# SCH_HOME_2023-08-20.net
KiCad netlist of a schematic drawn in EasyEDA
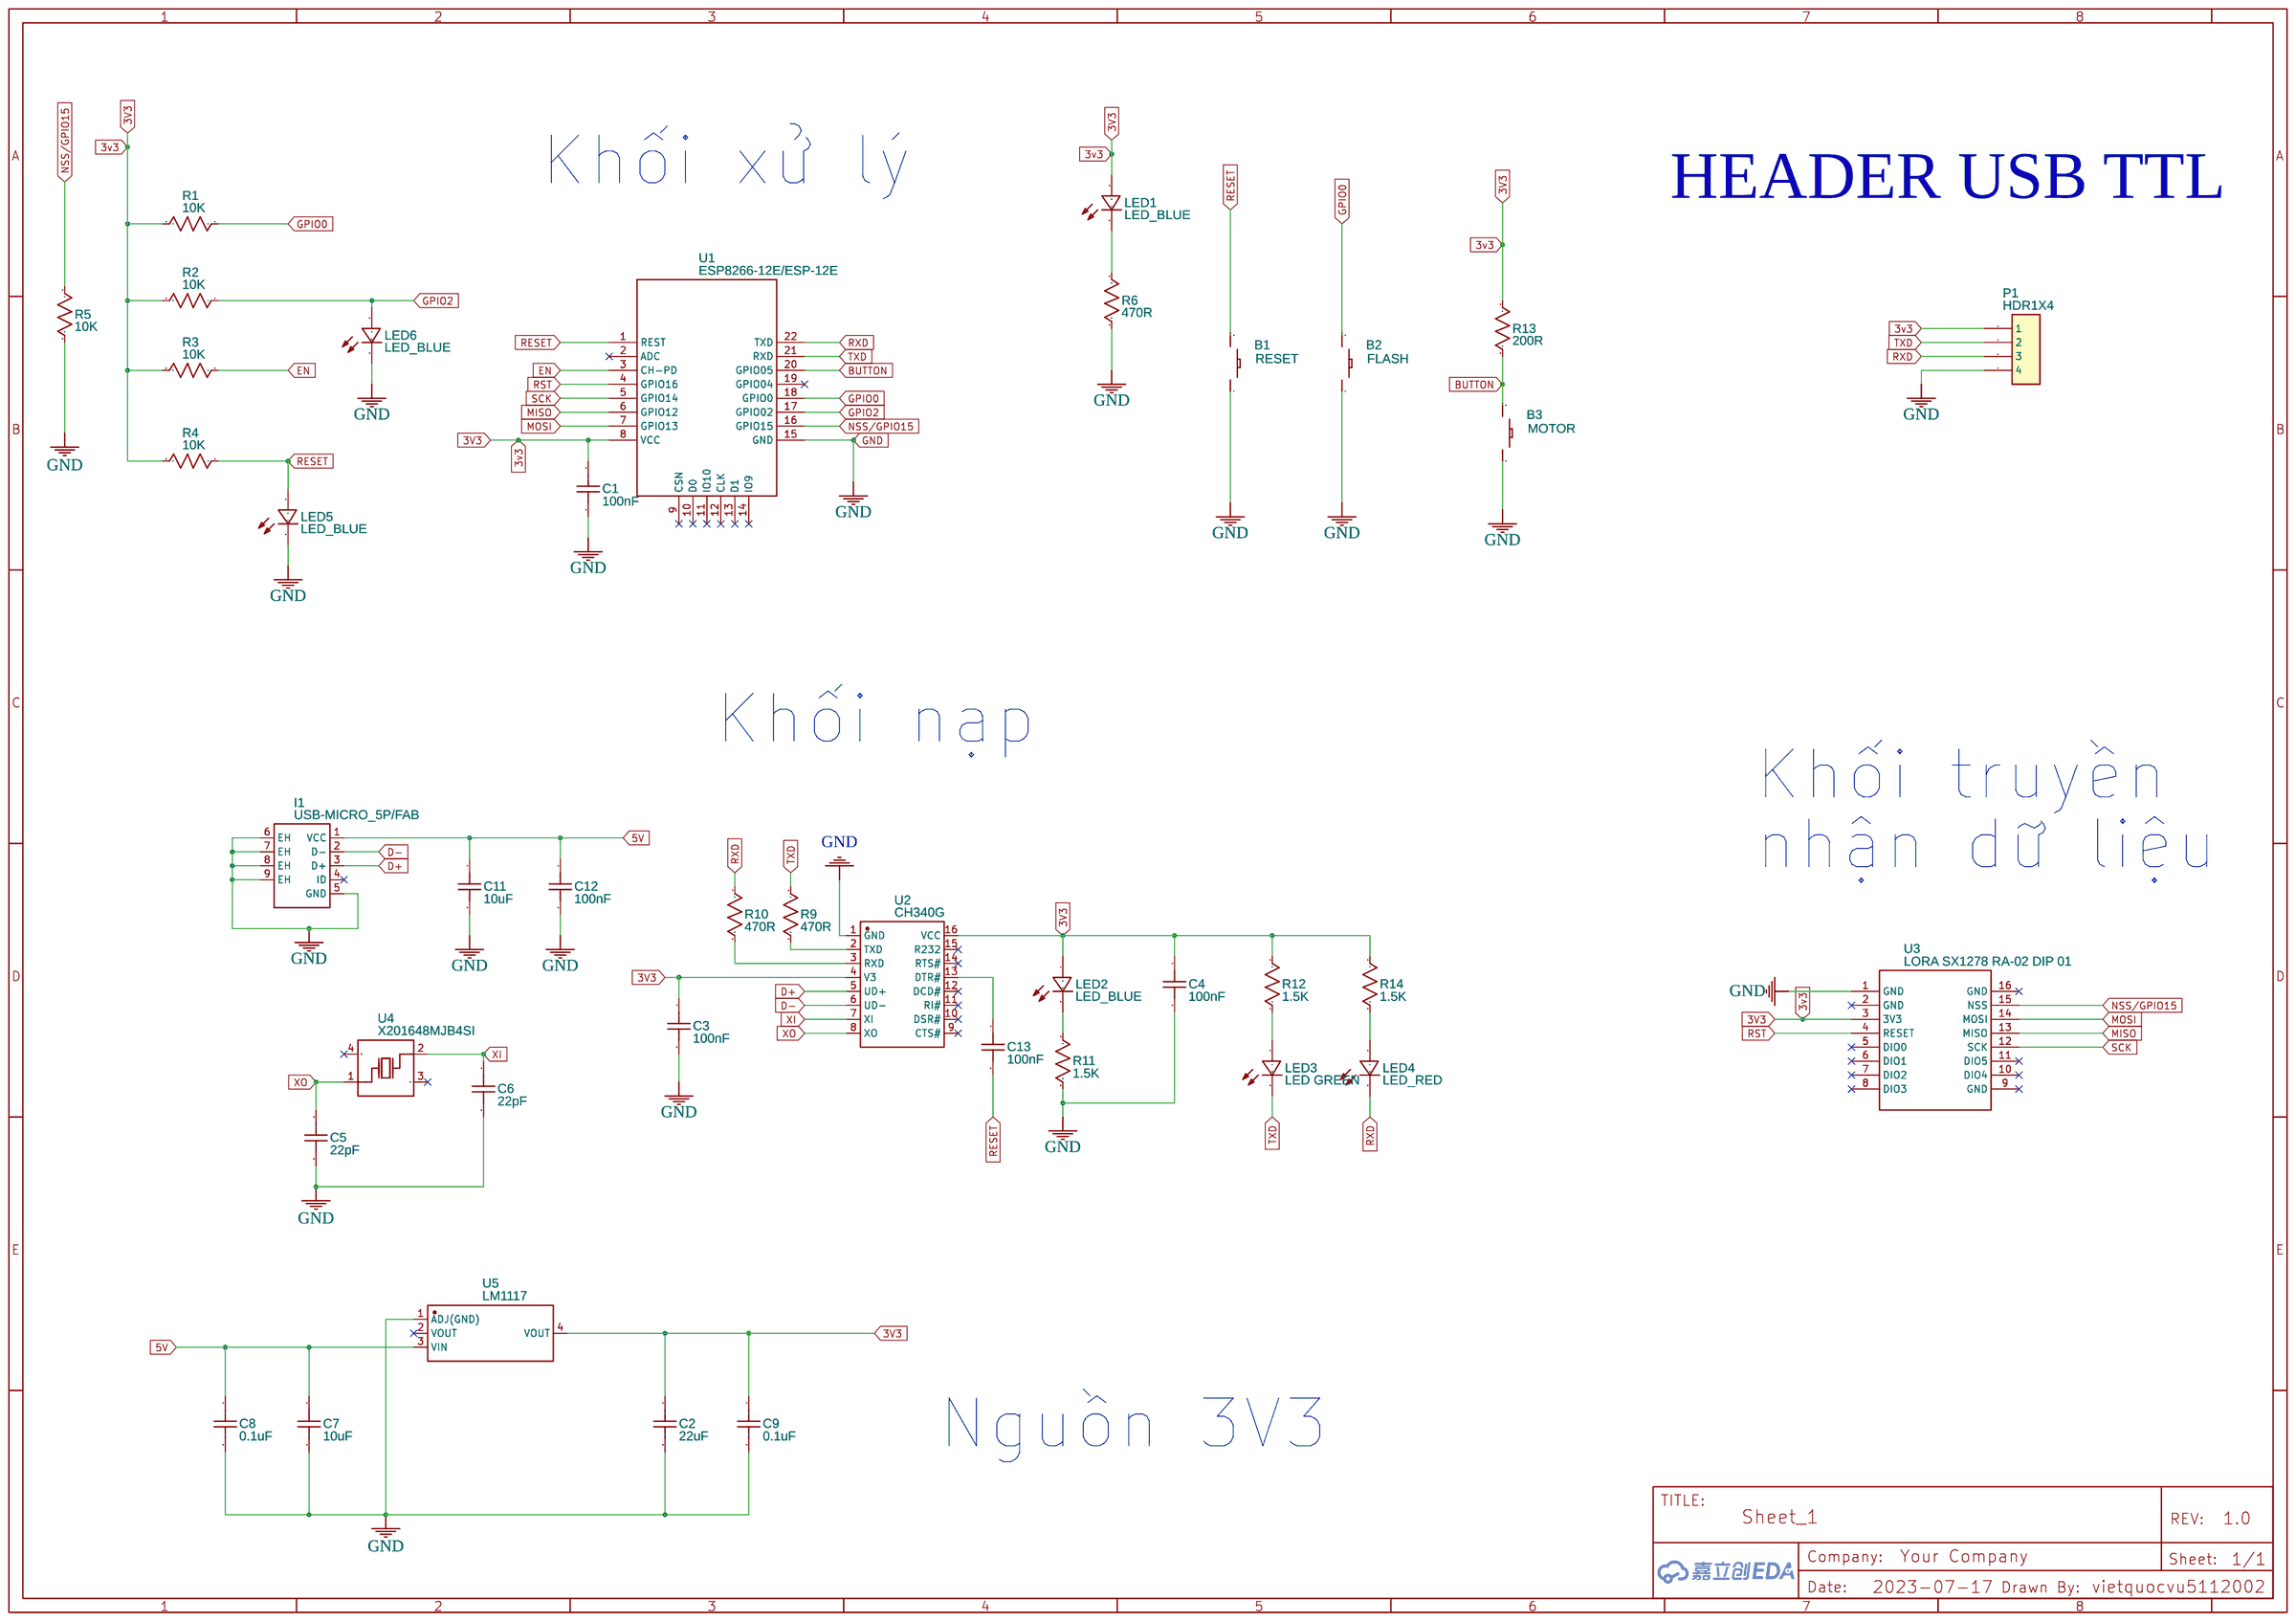
[diagram p0: schematic sheet]

(export (version "E")
  (design (tool "Eeschema 10.0.6"))
  (components
    (comp (ref "B1") (value "RESET") (libsource (lib "") (part "button")))
    (comp (ref "B2") (value "FLASH") (libsource (lib "") (part "button")))
    (comp (ref "B3") (value "MOTOR") (libsource (lib "") (part "button")))
    (comp (ref "C1") (value "100nF") (libsource (lib "") (part "C_0603_US_1")))
    (comp (ref "C2") (value "22uF") (libsource (lib "") (part "C_0603_US")))
    (comp (ref "C3") (value "100nF") (libsource (lib "") (part "C_0603_US")))
    (comp (ref "C4") (value "100nF") (libsource (lib "") (part "C_0603_US")))
    (comp (ref "C5") (value "22pF") (libsource (lib "") (part "C_0603_US")))
    (comp (ref "C6") (value "22pF") (libsource (lib "") (part "C_0603_US")))
    (comp (ref "C7") (value "10uF") (libsource (lib "") (part "C_0603_US")))
    (comp (ref "C8") (value "0.1uF") (libsource (lib "") (part "C_0603_US")))
    (comp (ref "C9") (value "0.1uF") (libsource (lib "") (part "C_0603_US")))
    (comp (ref "C11") (value "10uF") (libsource (lib "") (part "C_0603_US")))
    (comp (ref "C12") (value "100nF") (libsource (lib "") (part "C_0603_US")))
    (comp (ref "C13") (value "100nF") (libsource (lib "") (part "C_0603_US")))
    (comp (ref "I1")
      (value "USB-MICRO_5P/FAB")
      (fields (field (name "BOM_Supplier Part") "C9900004593"))
      (libsource (lib "") (part "USB-MICRO_5P/FAB"))
    )
    (comp (ref "LED1")
      (value "LED_BLUE")
      (fields (field (name "BOM_Supplier Part") "C9900016117"))
      (libsource (lib "") (part "LED_BLUE"))
    )
    (comp (ref "LED2")
      (value "LED_BLUE")
      (fields (field (name "BOM_Supplier Part") "C9900016117"))
      (libsource (lib "") (part "LED_BLUE"))
    )
    (comp (ref "LED3")
      (value "LED GREEN")
      (fields
        (field (name "BOM_Manufacturer Part") "LED_BLUE")
        (field (name "BOM_Supplier Part") "C9900016117")
      )
      (libsource (lib "") (part "LED_BLUE"))
    )
    (comp (ref "LED4")
      (value "LED_RED")
      (fields
        (field (name "BOM_Manufacturer Part") "LED_BLUE")
        (field (name "BOM_Supplier Part") "C9900016117")
      )
      (libsource (lib "") (part "LED_BLUE"))
    )
    (comp (ref "LED5")
      (value "LED_BLUE")
      (fields (field (name "BOM_Supplier Part") "C9900016117"))
      (libsource (lib "") (part "LED_BLUE"))
    )
    (comp (ref "LED6")
      (value "LED_BLUE")
      (fields (field (name "BOM_Supplier Part") "C9900016117"))
      (libsource (lib "") (part "LED_BLUE"))
    )
    (comp (ref "P1") (value "HDR1X4") (libsource (lib "") (part "HDR1X4")))
    (comp (ref "R1") (value "10K") (libsource (lib "") (part "R_0603_US")))
    (comp (ref "R2") (value "10K") (libsource (lib "") (part "R_0603_US")))
    (comp (ref "R3") (value "10K") (libsource (lib "") (part "R_0603_US")))
    (comp (ref "R4") (value "10K") (libsource (lib "") (part "R_0603_US")))
    (comp (ref "R5") (value "10K") (libsource (lib "") (part "R_0603_US_1")))
    (comp (ref "R6") (value "470R") (libsource (lib "") (part "R_0603_US_1")))
    (comp (ref "R9") (value "470R") (libsource (lib "") (part "R_0603_US_1")))
    (comp (ref "R10") (value "470R") (libsource (lib "") (part "R_0603_US_1")))
    (comp (ref "R11") (value "1.5K") (libsource (lib "") (part "R_0603_US_1")))
    (comp (ref "R12") (value "1.5K") (libsource (lib "") (part "R_0603_US_1")))
    (comp (ref "R13") (value "200R") (libsource (lib "") (part "R_0603_US_1")))
    (comp (ref "R14") (value "1.5K") (libsource (lib "") (part "R_0603_US_1")))
    (comp (ref "U1") (value "ESP8266-12E/ESP-12E") (libsource (lib "") (part "ESP8266-12E/ESP-12E")))
    (comp (ref "U2")
      (value "CH340G")
      (fields (field (name "BOM_Supplier Part") "C14267"))
      (libsource (lib "") (part "CH340G"))
    )
    (comp (ref "U3")
      (value "LORA SX1278 RA-02 DIP 01")
      (libsource (lib "") (part "LORA SX1278 RA-02 DIP 01"))
    )
    (comp (ref "U4")
      (value "X201648MJB4SI")
      (fields (field (name "BOM_Supplier Part") "C9900016209"))
      (libsource (lib "") (part "X201648MJB4SI"))
    )
    (comp (ref "U5")
      (value "LM1117")
      (fields
        (field (name "BOM_Manufacturer Part") "AMS1117-ADJ")
        (field (name "BOM_Supplier Part") "C2891840")
      )
      (libsource (lib "") (part "AMS1117-ADJ_C2891840"))
    )
  )
  (nets
    (net (code "1") (name "3V3") (class "Default")
      (node (ref "C1") (pin "2") (pinfunction "2_2") (pintype "unspecified"))
      (node (ref "C2") (pin "1") (pinfunction "1_1") (pintype "unspecified"))
      (node (ref "C3") (pin "1") (pinfunction "1_1") (pintype "unspecified"))
      (node (ref "C4") (pin "1") (pinfunction "1_1") (pintype "unspecified"))
      (node (ref "C9") (pin "1") (pinfunction "1_1") (pintype "unspecified"))
      (node (ref "LED1") (pin "1") (pinfunction "1_1") (pintype "unspecified"))
      (node (ref "LED2") (pin "1") (pinfunction "1_1") (pintype "unspecified"))
      (node (ref "P1") (pin "1") (pinfunction "1_1") (pintype "unspecified"))
      (node (ref "R1") (pin "2") (pinfunction "2_2") (pintype "unspecified"))
      (node (ref "R12") (pin "1") (pinfunction "1_1") (pintype "unspecified"))
      (node (ref "R13") (pin "1") (pinfunction "1_1") (pintype "unspecified"))
      (node (ref "R14") (pin "1") (pinfunction "1_1") (pintype "unspecified"))
      (node (ref "R2") (pin "2") (pinfunction "2_2") (pintype "unspecified"))
      (node (ref "R3") (pin "2") (pinfunction "2_2") (pintype "unspecified"))
      (node (ref "R4") (pin "2") (pinfunction "2_2") (pintype "unspecified"))
      (node (ref "U1") (pin "8") (pinfunction "VCC_8") (pintype "unspecified"))
      (node (ref "U2") (pin "16") (pinfunction "VCC_16") (pintype "unspecified"))
      (node (ref "U2") (pin "4") (pinfunction "V3_4") (pintype "unspecified"))
      (node (ref "U3") (pin "3") (pinfunction "3V3_3") (pintype "unspecified"))
      (node (ref "U5") (pin "4") (pinfunction "VOUT_4") (pintype "unspecified"))
    )
    (net (code "2") (name "5V") (class "Default")
      (node (ref "C11") (pin "1") (pinfunction "1_1") (pintype "unspecified"))
      (node (ref "C12") (pin "1") (pinfunction "1_1") (pintype "unspecified"))
      (node (ref "C7") (pin "1") (pinfunction "1_1") (pintype "unspecified"))
      (node (ref "C8") (pin "1") (pinfunction "1_1") (pintype "unspecified"))
      (node (ref "I1") (pin "1") (pinfunction "VCC_1") (pintype "input"))
      (node (ref "U5") (pin "3") (pinfunction "VIN_3") (pintype "unspecified"))
    )
    (net (code "3") (name "BUTTON") (class "Default")
      (node (ref "B3") (pin "3") (pinfunction "2_3") (pintype "unspecified"))
      (node (ref "R13") (pin "2") (pinfunction "2_2") (pintype "unspecified"))
      (node (ref "U1") (pin "20") (pinfunction "GPIO05_20") (pintype "unspecified"))
    )
    (net (code "4") (name "D+") (class "Default")
      (node (ref "I1") (pin "3") (pinfunction "D+_3") (pintype "input"))
      (node (ref "U2") (pin "5") (pinfunction "UD+_5") (pintype "unspecified"))
    )
    (net (code "5") (name "D-") (class "Default")
      (node (ref "I1") (pin "2") (pinfunction "D-_2") (pintype "input"))
      (node (ref "U2") (pin "6") (pinfunction "UD-_6") (pintype "unspecified"))
    )
    (net (code "6") (name "EN") (class "Default")
      (node (ref "R3") (pin "1") (pinfunction "1_1") (pintype "unspecified"))
      (node (ref "U1") (pin "3") (pinfunction "CH-PD_3") (pintype "unspecified"))
    )
    (net (code "7") (name "GND") (class "Default")
      (node (ref "B1") (pin "1") (pinfunction "1_1") (pintype "unspecified"))
      (node (ref "B2") (pin "1") (pinfunction "1_1") (pintype "unspecified"))
      (node (ref "B3") (pin "1") (pinfunction "1_1") (pintype "unspecified"))
      (node (ref "C1") (pin "1") (pinfunction "1_1") (pintype "unspecified"))
      (node (ref "C11") (pin "2") (pinfunction "2_2") (pintype "unspecified"))
      (node (ref "C12") (pin "2") (pinfunction "2_2") (pintype "unspecified"))
      (node (ref "C2") (pin "2") (pinfunction "2_2") (pintype "unspecified"))
      (node (ref "C3") (pin "2") (pinfunction "2_2") (pintype "unspecified"))
      (node (ref "C4") (pin "2") (pinfunction "2_2") (pintype "unspecified"))
      (node (ref "C5") (pin "2") (pinfunction "2_2") (pintype "unspecified"))
      (node (ref "C6") (pin "2") (pinfunction "2_2") (pintype "unspecified"))
      (node (ref "C7") (pin "2") (pinfunction "2_2") (pintype "unspecified"))
      (node (ref "C8") (pin "2") (pinfunction "2_2") (pintype "unspecified"))
      (node (ref "C9") (pin "2") (pinfunction "2_2") (pintype "unspecified"))
      (node (ref "I1") (pin "5") (pinfunction "GND_5") (pintype "input"))
      (node (ref "I1") (pin "6") (pinfunction "EH_6") (pintype "unspecified"))
      (node (ref "I1") (pin "7") (pinfunction "EH_7") (pintype "unspecified"))
      (node (ref "I1") (pin "8") (pinfunction "EH_8") (pintype "unspecified"))
      (node (ref "I1") (pin "9") (pinfunction "EH_9") (pintype "unspecified"))
      (node (ref "LED5") (pin "2") (pinfunction "2_2") (pintype "unspecified"))
      (node (ref "LED6") (pin "2") (pinfunction "2_2") (pintype "unspecified"))
      (node (ref "P1") (pin "4") (pinfunction "4_4") (pintype "unspecified"))
      (node (ref "R11") (pin "2") (pinfunction "2_2") (pintype "unspecified"))
      (node (ref "R5") (pin "2") (pinfunction "2_2") (pintype "unspecified"))
      (node (ref "R6") (pin "2") (pinfunction "2_2") (pintype "unspecified"))
      (node (ref "U1") (pin "15") (pinfunction "GND_15") (pintype "unspecified"))
      (node (ref "U2") (pin "1") (pinfunction "GND_1") (pintype "unspecified"))
      (node (ref "U3") (pin "1") (pinfunction "GND_1") (pintype "unspecified"))
      (node (ref "U5") (pin "1") (pinfunction "ADJ(GND)_1") (pintype "unspecified"))
    )
    (net (code "8") (name "GPIO0") (class "Default")
      (node (ref "B2") (pin "3") (pinfunction "2_3") (pintype "unspecified"))
      (node (ref "R1") (pin "1") (pinfunction "1_1") (pintype "unspecified"))
      (node (ref "U1") (pin "18") (pinfunction "GPIO0_18") (pintype "unspecified"))
    )
    (net (code "9") (name "GPIO2") (class "Default")
      (node (ref "LED6") (pin "1") (pinfunction "1_1") (pintype "unspecified"))
      (node (ref "R2") (pin "1") (pinfunction "1_1") (pintype "unspecified"))
      (node (ref "U1") (pin "17") (pinfunction "GPIO02_17") (pintype "unspecified"))
    )
    (net (code "10") (name "MISO") (class "Default")
      (node (ref "U1") (pin "6") (pinfunction "GPIO12_6") (pintype "unspecified"))
      (node (ref "U3") (pin "13") (pinfunction "MISO_13") (pintype "unspecified"))
    )
    (net (code "11") (name "MOSI") (class "Default")
      (node (ref "U1") (pin "7") (pinfunction "GPIO13_7") (pintype "unspecified"))
      (node (ref "U3") (pin "14") (pinfunction "MOSI_14") (pintype "unspecified"))
    )
    (net (code "12") (name "NSS{slash}GPIO15") (class "Default")
      (node (ref "R5") (pin "1") (pinfunction "1_1") (pintype "unspecified"))
      (node (ref "U1") (pin "16") (pinfunction "GPIO15_16") (pintype "unspecified"))
      (node (ref "U3") (pin "15") (pinfunction "NSS_15") (pintype "unspecified"))
    )
    (net (code "13") (name "Net-(LED1-Pad2)") (class "Default")
      (node (ref "LED1") (pin "2") (pinfunction "2_2") (pintype "unspecified"))
      (node (ref "R6") (pin "1") (pinfunction "1_1") (pintype "unspecified"))
    )
    (net (code "14") (name "Net-(LED2-Pad2)") (class "Default")
      (node (ref "LED2") (pin "2") (pinfunction "2_2") (pintype "unspecified"))
      (node (ref "R11") (pin "1") (pinfunction "1_1") (pintype "unspecified"))
    )
    (net (code "15") (name "Net-(LED3-Pad1)") (class "Default")
      (node (ref "LED3") (pin "1") (pinfunction "1_1") (pintype "unspecified"))
      (node (ref "R12") (pin "2") (pinfunction "2_2") (pintype "unspecified"))
    )
    (net (code "16") (name "Net-(LED4-Pad1)") (class "Default")
      (node (ref "LED4") (pin "1") (pinfunction "1_1") (pintype "unspecified"))
      (node (ref "R14") (pin "2") (pinfunction "2_2") (pintype "unspecified"))
    )
    (net (code "17") (name "Net-(U2-DTR#)") (class "Default")
      (node (ref "C13") (pin "1") (pinfunction "1_1") (pintype "unspecified"))
      (node (ref "U2") (pin "13") (pinfunction "DTR#_13") (pintype "unspecified"))
    )
    (net (code "18") (name "Net-(U2-RXD)") (class "Default")
      (node (ref "R10") (pin "2") (pinfunction "2_2") (pintype "unspecified"))
      (node (ref "U2") (pin "3") (pinfunction "RXD_3") (pintype "unspecified"))
    )
    (net (code "19") (name "Net-(U2-TXD)") (class "Default")
      (node (ref "R9") (pin "2") (pinfunction "2_2") (pintype "unspecified"))
      (node (ref "U2") (pin "2") (pinfunction "TXD_2") (pintype "unspecified"))
    )
    (net (code "20") (name "RESET") (class "Default")
      (node (ref "B1") (pin "3") (pinfunction "2_3") (pintype "unspecified"))
      (node (ref "C13") (pin "2") (pinfunction "2_2") (pintype "unspecified"))
      (node (ref "LED5") (pin "1") (pinfunction "1_1") (pintype "unspecified"))
      (node (ref "R4") (pin "1") (pinfunction "1_1") (pintype "unspecified"))
      (node (ref "U1") (pin "1") (pinfunction "REST_1") (pintype "unspecified"))
    )
    (net (code "21") (name "RST") (class "Default")
      (node (ref "U1") (pin "4") (pinfunction "GPIO16_4") (pintype "unspecified"))
      (node (ref "U3") (pin "4") (pinfunction "RESET_4") (pintype "unspecified"))
    )
    (net (code "22") (name "RXD") (class "Default")
      (node (ref "LED4") (pin "2") (pinfunction "2_2") (pintype "unspecified"))
      (node (ref "P1") (pin "3") (pinfunction "3_3") (pintype "unspecified"))
      (node (ref "R10") (pin "1") (pinfunction "1_1") (pintype "unspecified"))
      (node (ref "U1") (pin "22") (pinfunction "TXD_22") (pintype "unspecified"))
    )
    (net (code "23") (name "SCK") (class "Default")
      (node (ref "U1") (pin "5") (pinfunction "GPIO14_5") (pintype "unspecified"))
      (node (ref "U3") (pin "12") (pinfunction "SCK_12") (pintype "unspecified"))
    )
    (net (code "24") (name "TXD") (class "Default")
      (node (ref "LED3") (pin "2") (pinfunction "2_2") (pintype "unspecified"))
      (node (ref "P1") (pin "2") (pinfunction "2_2") (pintype "unspecified"))
      (node (ref "R9") (pin "1") (pinfunction "1_1") (pintype "unspecified"))
      (node (ref "U1") (pin "21") (pinfunction "RXD_21") (pintype "unspecified"))
    )
    (net (code "25") (name "XI") (class "Default")
      (node (ref "C6") (pin "1") (pinfunction "1_1") (pintype "unspecified"))
      (node (ref "U2") (pin "7") (pinfunction "XI_7") (pintype "unspecified"))
      (node (ref "U4") (pin "2") (pinfunction "OSC2_2") (pintype "unspecified"))
    )
    (net (code "26") (name "XO") (class "Default")
      (node (ref "C5") (pin "1") (pinfunction "1_1") (pintype "unspecified"))
      (node (ref "U2") (pin "8") (pinfunction "XO_8") (pintype "unspecified"))
      (node (ref "U4") (pin "1") (pinfunction "OSC1_1") (pintype "unspecified"))
    )
    (net (code "27") (name "unconnected-(I1-ID-Pad4)") (class "Default")
      (node (ref "I1") (pin "4") (pinfunction "ID_4") (pintype "input+no_connect"))
    )
    (net (code "28") (name "unconnected-(U1-ADC-Pad2)") (class "Default")
      (node (ref "U1") (pin "2") (pinfunction "ADC_2") (pintype "unspecified+no_connect"))
    )
    (net (code "29") (name "unconnected-(U1-CLK-Pad12)") (class "Default")
      (node (ref "U1") (pin "12") (pinfunction "CLK_12") (pintype "unspecified+no_connect"))
    )
    (net (code "30") (name "unconnected-(U1-CSN-Pad9)") (class "Default")
      (node (ref "U1") (pin "9") (pinfunction "CSN_9") (pintype "unspecified+no_connect"))
    )
    (net (code "31") (name "unconnected-(U1-D0-Pad10)") (class "Default")
      (node (ref "U1") (pin "10") (pinfunction "D0_10") (pintype "unspecified+no_connect"))
    )
    (net (code "32") (name "unconnected-(U1-D1-Pad13)") (class "Default")
      (node (ref "U1") (pin "13") (pinfunction "D1_13") (pintype "unspecified+no_connect"))
    )
    (net (code "33") (name "unconnected-(U1-GPIO04-Pad19)") (class "Default")
      (node (ref "U1") (pin "19") (pinfunction "GPIO04_19") (pintype "unspecified+no_connect"))
    )
    (net (code "34") (name "unconnected-(U1-IO9-Pad14)") (class "Default")
      (node (ref "U1") (pin "14") (pinfunction "IO9_14") (pintype "unspecified+no_connect"))
    )
    (net (code "35") (name "unconnected-(U1-IO10-Pad11)") (class "Default")
      (node (ref "U1") (pin "11") (pinfunction "IO10_11") (pintype "unspecified+no_connect"))
    )
    (net (code "36") (name "unconnected-(U2-CTS#-Pad9)") (class "Default")
      (node (ref "U2") (pin "9") (pinfunction "CTS#_9") (pintype "unspecified+no_connect"))
    )
    (net (code "37") (name "unconnected-(U2-DCD#-Pad12)") (class "Default")
      (node (ref "U2") (pin "12") (pinfunction "DCD#_12") (pintype "unspecified+no_connect"))
    )
    (net (code "38") (name "unconnected-(U2-DSR#-Pad10)") (class "Default")
      (node (ref "U2") (pin "10") (pinfunction "DSR#_10") (pintype "unspecified+no_connect"))
    )
    (net (code "39") (name "unconnected-(U2-R232-Pad15)") (class "Default")
      (node (ref "U2") (pin "15") (pinfunction "R232_15") (pintype "unspecified+no_connect"))
    )
    (net (code "40") (name "unconnected-(U2-RI#-Pad11)") (class "Default")
      (node (ref "U2") (pin "11") (pinfunction "RI#_11") (pintype "unspecified+no_connect"))
    )
    (net (code "41") (name "unconnected-(U2-RTS#-Pad14)") (class "Default")
      (node (ref "U2") (pin "14") (pinfunction "RTS#_14") (pintype "unspecified+no_connect"))
    )
    (net (code "42") (name "unconnected-(U3-DIO0-Pad5)") (class "Default")
      (node (ref "U3") (pin "5") (pinfunction "DIO0_5") (pintype "unspecified+no_connect"))
    )
    (net (code "43") (name "unconnected-(U3-DIO1-Pad6)") (class "Default")
      (node (ref "U3") (pin "6") (pinfunction "DIO1_6") (pintype "unspecified+no_connect"))
    )
    (net (code "44") (name "unconnected-(U3-DIO2-Pad7)") (class "Default")
      (node (ref "U3") (pin "7") (pinfunction "DIO2_7") (pintype "unspecified+no_connect"))
    )
    (net (code "45") (name "unconnected-(U3-DIO3-Pad8)") (class "Default")
      (node (ref "U3") (pin "8") (pinfunction "DIO3_8") (pintype "unspecified+no_connect"))
    )
    (net (code "46") (name "unconnected-(U3-DIO4-Pad10)") (class "Default")
      (node (ref "U3") (pin "10") (pinfunction "DIO4_10") (pintype "unspecified+no_connect"))
    )
    (net (code "47") (name "unconnected-(U3-DIO5-Pad11)") (class "Default")
      (node (ref "U3") (pin "11") (pinfunction "DIO5_11") (pintype "unspecified+no_connect"))
    )
    (net (code "48") (name "unconnected-(U3-GND-Pad2)") (class "Default")
      (node (ref "U3") (pin "2") (pinfunction "GND_2") (pintype "unspecified+no_connect"))
    )
    (net (code "49") (name "unconnected-(U3-GND-Pad9)") (class "Default")
      (node (ref "U3") (pin "9") (pinfunction "GND_9") (pintype "unspecified+no_connect"))
    )
    (net (code "50") (name "unconnected-(U3-GND-Pad16)") (class "Default")
      (node (ref "U3") (pin "16") (pinfunction "GND_16") (pintype "unspecified+no_connect"))
    )
    (net (code "51") (name "unconnected-(U4-GND-Pad3)") (class "Default")
      (node (ref "U4") (pin "3") (pinfunction "GND_3") (pintype "unspecified+no_connect"))
    )
    (net (code "52") (name "unconnected-(U4-GND-Pad4)") (class "Default")
      (node (ref "U4") (pin "4") (pinfunction "GND_4") (pintype "unspecified+no_connect"))
    )
    (net (code "53") (name "unconnected-(U5-VOUT-Pad2)") (class "Default")
      (node (ref "U5") (pin "2") (pinfunction "VOUT_2") (pintype "unspecified+no_connect"))
    )
  )
)
